# Alim.net
KiCad netlist of a schematic drawn in Altium Designer
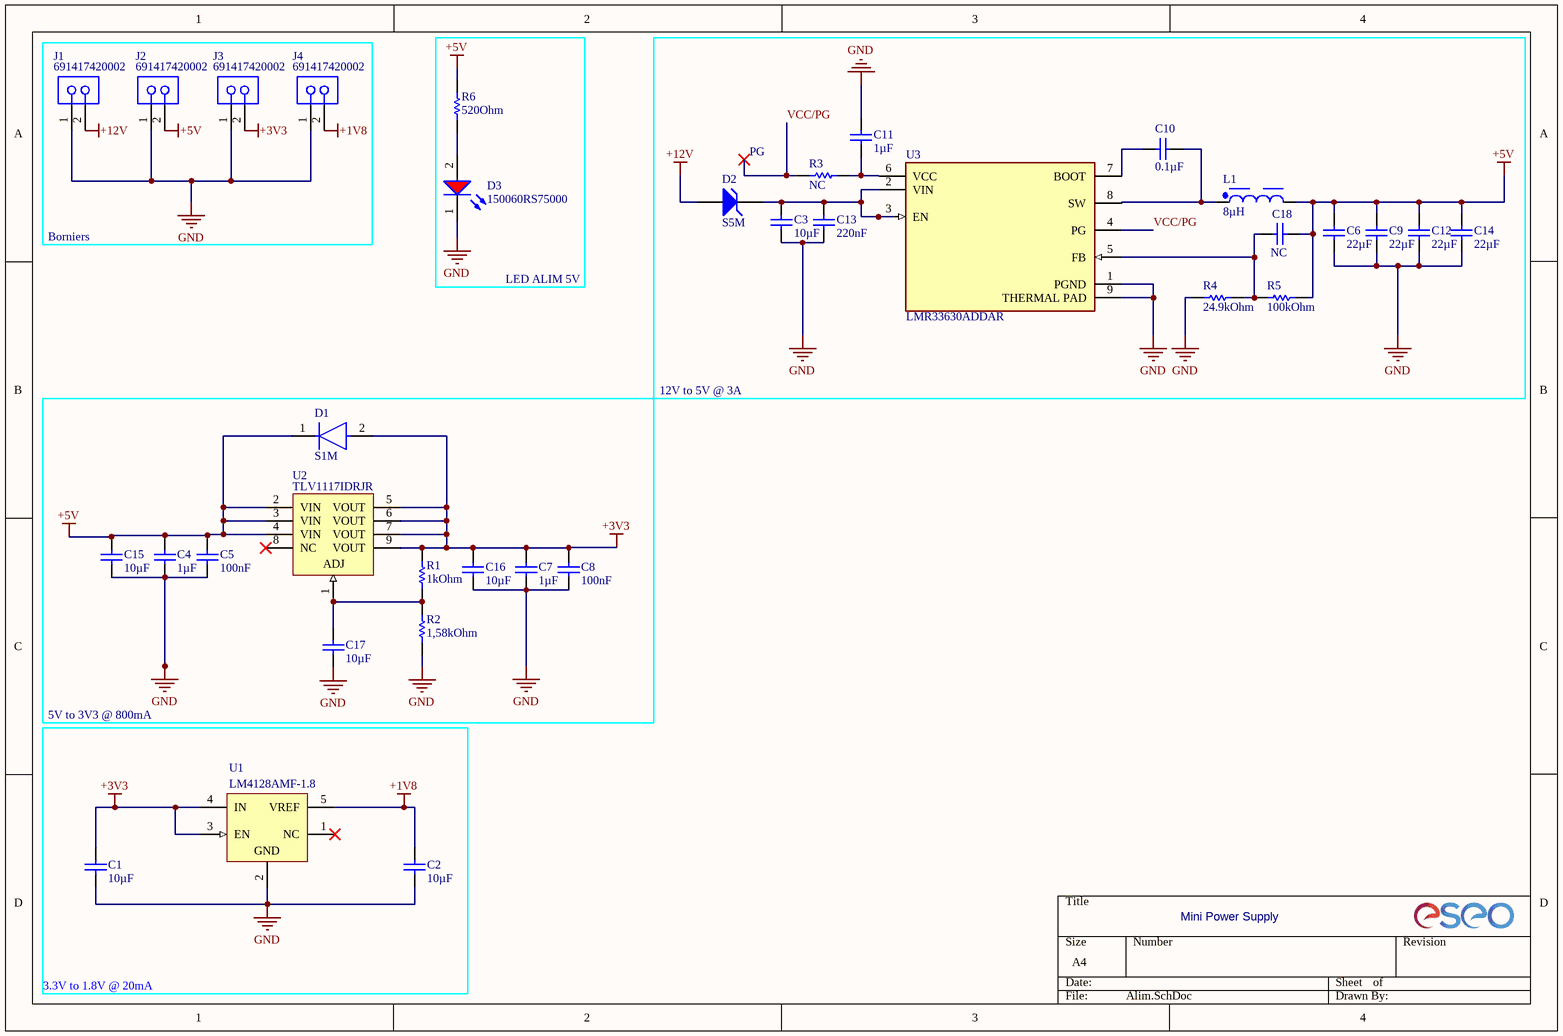
[diagram p0: Alim.SchDoc]

(export (version "E")
  (design (tool "Eeschema 10.0.6"))
  (components
    (comp (ref "C1")
      (value "10µF")
      (footprint "CONDENSATEUR_CMS_1210")
      (description "CONDENSATEUR CMS CERAMIQUE 1210")
      (fields (field (name "Comment") "CMS_1210"))
      (libsource (lib "Alim") (part "CONDENSATEUR_CMS_CER_1210"))
    )
    (comp (ref "C2")
      (value "10µF")
      (footprint "CONDENSATEUR_CMS_1210")
      (description "CONDENSATEUR CMS CERAMIQUE 1210")
      (fields (field (name "Comment") "CMS_1210"))
      (libsource (lib "Alim") (part "CONDENSATEUR_CMS_CER_1210"))
    )
    (comp (ref "C3")
      (value "10µF")
      (footprint "CONDENSATEUR_CMS_1210")
      (description "CONDENSATEUR CMS CERAMIQUE 1210")
      (fields (field (name "Comment") "CMS_1210"))
      (libsource (lib "Alim") (part "CONDENSATEUR_CMS_CER_1210"))
    )
    (comp (ref "C4")
      (value "1µF")
      (footprint "CONDENSATEUR_CMS_0603")
      (description "CONDENSATEUR CMS CERAMIQUE 0603")
      (fields (field (name "Comment") "CMS_0603"))
      (libsource (lib "Alim") (part "CONDENSATEUR_CMS_CER_0603"))
    )
    (comp (ref "C5")
      (value "100nF")
      (footprint "CONDENSATEUR_CMS_0603")
      (description "CONDENSATEUR CMS CERAMIQUE 0603")
      (fields (field (name "Comment") "CMS_0603"))
      (libsource (lib "Alim") (part "CONDENSATEUR_CMS_CER_0603"))
    )
    (comp (ref "C6")
      (value "22µF")
      (footprint "CONDENSATEUR_CMS_1210")
      (description "CONDENSATEUR CMS CERAMIQUE 1210")
      (fields (field (name "Comment") "CMS_1210"))
      (libsource (lib "Alim") (part "CONDENSATEUR_CMS_CER_1210"))
    )
    (comp (ref "C7")
      (value "1µF")
      (footprint "CONDENSATEUR_CMS_0603")
      (description "CONDENSATEUR CMS CERAMIQUE 0603")
      (fields (field (name "Comment") "CMS_0603"))
      (libsource (lib "Alim") (part "CONDENSATEUR_CMS_CER_0603"))
    )
    (comp (ref "C8")
      (value "100nF")
      (footprint "CONDENSATEUR_CMS_0603")
      (description "CONDENSATEUR CMS CERAMIQUE 0603")
      (fields (field (name "Comment") "CMS_0603"))
      (libsource (lib "Alim") (part "CONDENSATEUR_CMS_CER_0603"))
    )
    (comp (ref "C9")
      (value "22µF")
      (footprint "CONDENSATEUR_CMS_1210")
      (description "CONDENSATEUR CMS CERAMIQUE 1210")
      (fields (field (name "Comment") "CMS_1210"))
      (libsource (lib "Alim") (part "CONDENSATEUR_CMS_CER_1210"))
    )
    (comp (ref "C10")
      (value "0.1µF")
      (footprint "CONDENSATEUR_CMS_0603")
      (description "CONDENSATEUR CMS CERAMIQUE 0603")
      (fields (field (name "Comment") "CMS_0603"))
      (libsource (lib "Alim") (part "CONDENSATEUR_CMS_CER_0603"))
    )
    (comp (ref "C11")
      (value "1µF")
      (footprint "CONDENSATEUR_CMS_0603")
      (description "CONDENSATEUR CMS CERAMIQUE 0603")
      (fields (field (name "Comment") "CMS_0603"))
      (libsource (lib "Alim") (part "CONDENSATEUR_CMS_CER_0603"))
    )
    (comp (ref "C12")
      (value "22µF")
      (footprint "CONDENSATEUR_CMS_1210")
      (description "CONDENSATEUR CMS CERAMIQUE 1210")
      (fields (field (name "Comment") "CMS_1210"))
      (libsource (lib "Alim") (part "CONDENSATEUR_CMS_CER_1210"))
    )
    (comp (ref "C13")
      (value "220nF")
      (footprint "CONDENSATEUR_CMS_0603")
      (description "CONDENSATEUR CMS CERAMIQUE 0603")
      (fields (field (name "Comment") "CMS_0603"))
      (libsource (lib "Alim") (part "CONDENSATEUR_CMS_CER_0603"))
    )
    (comp (ref "C14")
      (value "22µF")
      (footprint "CONDENSATEUR_CMS_1210")
      (description "CONDENSATEUR CMS CERAMIQUE 1210")
      (fields (field (name "Comment") "CMS_1210"))
      (libsource (lib "Alim") (part "CONDENSATEUR_CMS_CER_1210"))
    )
    (comp (ref "C15")
      (value "10µF")
      (footprint "CONDENSATEUR_CMS_1210")
      (description "CONDENSATEUR CMS CERAMIQUE 1210")
      (fields (field (name "Comment") "CMS_1210"))
      (libsource (lib "Alim") (part "CONDENSATEUR_CMS_CER_1210"))
    )
    (comp (ref "C16")
      (value "10µF")
      (footprint "CONDENSATEUR_CMS_1210")
      (description "CONDENSATEUR CMS CERAMIQUE 1210")
      (fields (field (name "Comment") "CMS_1210"))
      (libsource (lib "Alim") (part "CONDENSATEUR_CMS_CER_1210"))
    )
    (comp (ref "C17")
      (value "10µF")
      (footprint "CONDENSATEUR_CMS_1210")
      (description "CONDENSATEUR CMS CERAMIQUE 1210")
      (fields (field (name "Comment") "CMS_1210"))
      (libsource (lib "Alim") (part "CONDENSATEUR_CMS_CER_1210"))
    )
    (comp (ref "C18")
      (value "NC")
      (footprint "CONDENSATEUR_CMS_0603")
      (description "CONDENSATEUR CMS CERAMIQUE 0603")
      (fields (field (name "Comment") "CMS_0603"))
      (libsource (lib "Alim") (part "CONDENSATEUR_CMS_CER_0603"))
    )
    (comp (ref "D1")
      (value "S1M")
      (footprint "DO-214AC")
      (description "DIODE GEN PURP 1KV 1A SMA")
      (fields (field (name "VOLTAGE") "1kV"))
      (libsource (lib "Alim") (part "S1M"))
    )
    (comp (ref "D2")
      (value "S5M")
      (footprint "DO-214AB")
      (fields (field (name "MANUFACTURER") "Littelfuse-Inc."))
      (libsource (lib "Alim") (part "S5M"))
    )
    (comp (ref "D3")
      (value "150060RS75000")
      (footprint "LED_0603")
      (description "LED 0603 Générique")
      (libsource (lib "Alim") (part "LED 150060RS75000"))
    )
    (comp (ref "J1")
      (value "691417420002")
      (footprint "691417420002")
      (description "Bornier poussoir 7,62mm")
      (libsource (lib "Alim") (part "Bornier 691417420002"))
    )
    (comp (ref "J2")
      (value "691417420002")
      (footprint "691417420002")
      (description "Bornier poussoir 7,62mm")
      (libsource (lib "Alim") (part "Bornier 691417420002"))
    )
    (comp (ref "J3")
      (value "691417420002")
      (footprint "691417420002")
      (description "Bornier poussoir 7,62mm")
      (libsource (lib "Alim") (part "Bornier 691417420002"))
    )
    (comp (ref "J4")
      (value "691417420002")
      (footprint "691417420002")
      (description "Bornier poussoir 7,62mm")
      (libsource (lib "Alim") (part "Bornier 691417420002"))
    )
    (comp (ref "L1")
      (value "8µH")
      (footprint "WE-PDA_1260")
      (description "784771100 Inductor, Aec-Q200, 10Uh, Shld, 5A Rohs Compliant: Yes")
      (fields (field (name "TOLERANCE") "20%"))
      (libsource (lib "Alim") (part "Self 784771100"))
    )
    (comp (ref "R1")
      (value "1kOhm")
      (footprint "RESISTANCE_CMS_0603")
      (description "RESISTANCE CMS 0603")
      (fields (field (name "Comment") "RESISTANCE_CMS_0603"))
      (libsource (lib "Alim") (part "RESISTANCE_CMS_0603"))
    )
    (comp (ref "R2")
      (value "1,58kOhm")
      (footprint "RESISTANCE_CMS_0603")
      (description "RESISTANCE CMS 0603")
      (fields (field (name "Comment") "RESISTANCE_CMS_0603"))
      (libsource (lib "Alim") (part "RESISTANCE_CMS_0603"))
    )
    (comp (ref "R3")
      (value "NC")
      (footprint "RESISTANCE_CMS_0603")
      (description "RESISTANCE CMS 0603")
      (fields (field (name "Comment") "RESISTANCE_CMS_0603"))
      (libsource (lib "Alim") (part "RESISTANCE_CMS_0603"))
    )
    (comp (ref "R4")
      (value "24.9kOhm")
      (footprint "RESISTANCE_CMS_0603")
      (description "RESISTANCE CMS 0603")
      (fields (field (name "Comment") "RESISTANCE_CMS_0603"))
      (libsource (lib "Alim") (part "RESISTANCE_CMS_0603"))
    )
    (comp (ref "R5")
      (value "100kOhm")
      (footprint "RESISTANCE_CMS_0603")
      (description "RESISTANCE CMS 0603")
      (fields (field (name "Comment") "RESISTANCE_CMS_0603"))
      (libsource (lib "Alim") (part "RESISTANCE_CMS_0603"))
    )
    (comp (ref "R6")
      (value "520Ohm")
      (footprint "RESISTANCE_CMS_0603")
      (description "RESISTANCE CMS 0603")
      (fields (field (name "Comment") "RESISTANCE_CMS_0603"))
      (libsource (lib "Alim") (part "RESISTANCE_CMS_0603"))
    )
    (comp (ref "U1")
      (value "LM4128AMF-1.8")
      (footprint "SOT23-5")
      (description "Precision Micropower Series Voltage Reference, 5-pin SOT-23")
      (fields (field (name "MANUFACTURER") "National Semiconductor"))
      (libsource (lib "Alim") (part "LM4128AMF-1.8"))
    )
    (comp (ref "U2")
      (value "TLV1117IDRJR")
      (footprint "WSON-8")
      (fields (field (name "MANUFACTURER") "Texas Instruments"))
      (libsource (lib "Alim") (part "TLV1117IDRJR"))
    )
    (comp (ref "U3")
      (value "LMR33630ADDAR")
      (footprint "HSOIC")
      (description "IC REG BUCK ADJUSTABLE 3A 8SOPWR")
      (libsource (lib "Alim") (part "LMR33630ADDAR"))
    )
  )
  (nets
    (net (code "1") (name "+1V8") (class "Default")
      (node (ref "C2") (pin "2") (pinfunction "2_2") (pintype "passive"))
      (node (ref "J4") (pin "2") (pinfunction "2_2") (pintype "passive"))
      (node (ref "U1") (pin "5") (pinfunction "VREF_5") (pintype "power_in"))
    )
    (net (code "2") (name "+3V3") (class "Default")
      (node (ref "C1") (pin "2") (pinfunction "2_2") (pintype "passive"))
      (node (ref "C16") (pin "2") (pinfunction "2_2") (pintype "passive"))
      (node (ref "C7") (pin "2") (pinfunction "2_2") (pintype "passive"))
      (node (ref "C8") (pin "2") (pinfunction "2_2") (pintype "passive"))
      (node (ref "D1") (pin "2") (pinfunction "A_2") (pintype "passive"))
      (node (ref "J3") (pin "2") (pinfunction "2_2") (pintype "passive"))
      (node (ref "R1") (pin "2") (pinfunction "2_2") (pintype "passive"))
      (node (ref "U1") (pin "3") (pinfunction "EN_3") (pintype "input"))
      (node (ref "U1") (pin "4") (pinfunction "IN_4") (pintype "power_in"))
      (node (ref "U2") (pin "5") (pinfunction "VOUT_5") (pintype "power_in"))
      (node (ref "U2") (pin "6") (pinfunction "VOUT_6") (pintype "power_in"))
      (node (ref "U2") (pin "7") (pinfunction "VOUT_7") (pintype "power_in"))
      (node (ref "U2") (pin "9") (pinfunction "VOUT_9") (pintype "power_in"))
    )
    (net (code "3") (name "+5V") (class "Default")
      (node (ref "C12") (pin "2") (pinfunction "2_2") (pintype "passive"))
      (node (ref "C14") (pin "2") (pinfunction "2_2") (pintype "passive"))
      (node (ref "C15") (pin "2") (pinfunction "2_2") (pintype "passive"))
      (node (ref "C18") (pin "2") (pinfunction "2_2") (pintype "passive"))
      (node (ref "C4") (pin "2") (pinfunction "2_2") (pintype "passive"))
      (node (ref "C5") (pin "2") (pinfunction "2_2") (pintype "passive"))
      (node (ref "C6") (pin "2") (pinfunction "2_2") (pintype "passive"))
      (node (ref "C9") (pin "2") (pinfunction "2_2") (pintype "passive"))
      (node (ref "D1") (pin "1") (pinfunction "C_1") (pintype "passive"))
      (node (ref "J2") (pin "2") (pinfunction "2_2") (pintype "passive"))
      (node (ref "L1") (pin "2") (pinfunction "2_2") (pintype "passive"))
      (node (ref "R5") (pin "1") (pinfunction "1_1") (pintype "passive"))
      (node (ref "R6") (pin "2") (pinfunction "2_2") (pintype "passive"))
      (node (ref "U2") (pin "2") (pinfunction "VIN_2") (pintype "power_in"))
      (node (ref "U2") (pin "3") (pinfunction "VIN_3") (pintype "power_in"))
      (node (ref "U2") (pin "4") (pinfunction "VIN_4") (pintype "power_in"))
    )
    (net (code "4") (name "+12V") (class "Default")
      (node (ref "D2") (pin "1") (pinfunction "A_1") (pintype "passive"))
      (node (ref "J1") (pin "2") (pinfunction "2_2") (pintype "passive"))
    )
    (net (code "5") (name "/VCC{slash}PG") (class "Default")
      (node (ref "R3") (pin "1") (pinfunction "1_1") (pintype "passive"))
      (node (ref "U3") (pin "4") (pinfunction "PG_4") (pintype "open_collector"))
    )
    (net (code "6") (name "GND") (class "Default")
      (node (ref "C1") (pin "1") (pinfunction "1_1") (pintype "passive"))
      (node (ref "C11") (pin "2") (pinfunction "2_2") (pintype "passive"))
      (node (ref "C12") (pin "1") (pinfunction "1_1") (pintype "passive"))
      (node (ref "C13") (pin "1") (pinfunction "1_1") (pintype "passive"))
      (node (ref "C14") (pin "1") (pinfunction "1_1") (pintype "passive"))
      (node (ref "C15") (pin "1") (pinfunction "1_1") (pintype "passive"))
      (node (ref "C16") (pin "1") (pinfunction "1_1") (pintype "passive"))
      (node (ref "C17") (pin "1") (pinfunction "1_1") (pintype "passive"))
      (node (ref "C2") (pin "1") (pinfunction "1_1") (pintype "passive"))
      (node (ref "C3") (pin "1") (pinfunction "1_1") (pintype "passive"))
      (node (ref "C4") (pin "1") (pinfunction "1_1") (pintype "passive"))
      (node (ref "C5") (pin "1") (pinfunction "1_1") (pintype "passive"))
      (node (ref "C6") (pin "1") (pinfunction "1_1") (pintype "passive"))
      (node (ref "C7") (pin "1") (pinfunction "1_1") (pintype "passive"))
      (node (ref "C8") (pin "1") (pinfunction "1_1") (pintype "passive"))
      (node (ref "C9") (pin "1") (pinfunction "1_1") (pintype "passive"))
      (node (ref "D3") (pin "1") (pinfunction "K_1") (pintype "passive"))
      (node (ref "J1") (pin "1") (pinfunction "1_1") (pintype "passive"))
      (node (ref "J2") (pin "1") (pinfunction "1_1") (pintype "passive"))
      (node (ref "J3") (pin "1") (pinfunction "1_1") (pintype "passive"))
      (node (ref "J4") (pin "1") (pinfunction "1_1") (pintype "passive"))
      (node (ref "R2") (pin "1") (pinfunction "1_1") (pintype "passive"))
      (node (ref "R4") (pin "2") (pinfunction "2_2") (pintype "passive"))
      (node (ref "U1") (pin "2") (pinfunction "GND_2") (pintype "power_in"))
      (node (ref "U3") (pin "1") (pinfunction "PGND_1") (pintype "power_in"))
      (node (ref "U3") (pin "9") (pinfunction "THERMAL_PAD_9") (pintype "passive"))
    )
    (net (code "7") (name "Net-(D2-K)") (class "Default")
      (node (ref "C13") (pin "2") (pinfunction "2_2") (pintype "passive"))
      (node (ref "C3") (pin "2") (pinfunction "2_2") (pintype "passive"))
      (node (ref "D2") (pin "2") (pinfunction "K_2") (pintype "passive"))
      (node (ref "U3") (pin "2") (pinfunction "VIN_2") (pintype "power_in"))
      (node (ref "U3") (pin "3") (pinfunction "EN_3") (pintype "input"))
    )
    (net (code "8") (name "Net-(D3-A)") (class "Default")
      (node (ref "D3") (pin "2") (pinfunction "A_2") (pintype "passive"))
      (node (ref "R6") (pin "1") (pinfunction "1_1") (pintype "passive"))
    )
    (net (code "9") (name "Net-(U2-ADJ)") (class "Default")
      (node (ref "C17") (pin "2") (pinfunction "2_2") (pintype "passive"))
      (node (ref "R1") (pin "1") (pinfunction "1_1") (pintype "passive"))
      (node (ref "R2") (pin "2") (pinfunction "2_2") (pintype "passive"))
      (node (ref "U2") (pin "1") (pinfunction "ADJ_1") (pintype "input"))
    )
    (net (code "10") (name "Net-(U3-BOOT)") (class "Default")
      (node (ref "C10") (pin "1") (pinfunction "1_1") (pintype "passive"))
      (node (ref "U3") (pin "7") (pinfunction "BOOT_7") (pintype "passive"))
    )
    (net (code "11") (name "Net-(U3-FB)") (class "Default")
      (node (ref "C18") (pin "1") (pinfunction "1_1") (pintype "passive"))
      (node (ref "R4") (pin "1") (pinfunction "1_1") (pintype "passive"))
      (node (ref "R5") (pin "2") (pinfunction "2_2") (pintype "passive"))
      (node (ref "U3") (pin "5") (pinfunction "FB_5") (pintype "input"))
    )
    (net (code "12") (name "Net-(U3-SW)") (class "Default")
      (node (ref "C10") (pin "2") (pinfunction "2_2") (pintype "passive"))
      (node (ref "L1") (pin "1") (pinfunction "1_1") (pintype "passive"))
      (node (ref "U3") (pin "8") (pinfunction "SW_8") (pintype "passive"))
    )
    (net (code "13") (name "Net-(U3-VCC)") (class "Default")
      (node (ref "C11") (pin "1") (pinfunction "1_1") (pintype "passive"))
      (node (ref "R3") (pin "2") (pinfunction "2_2") (pintype "passive"))
      (node (ref "U3") (pin "6") (pinfunction "VCC_6") (pintype "power_in"))
    )
    (net (code "14") (name "unconnected-(U1-NC-Pad1)") (class "Default")
      (node (ref "U1") (pin "1") (pinfunction "NC_1") (pintype "passive+no_connect"))
    )
    (net (code "15") (name "unconnected-(U2-NC-Pad8)") (class "Default")
      (node (ref "U2") (pin "8") (pinfunction "NC_8") (pintype "passive+no_connect"))
    )
  )
)
